# SpaceDisplayOverheadLED_Schematic.net
KiCad netlist of a schematic drawn in Altium Designer
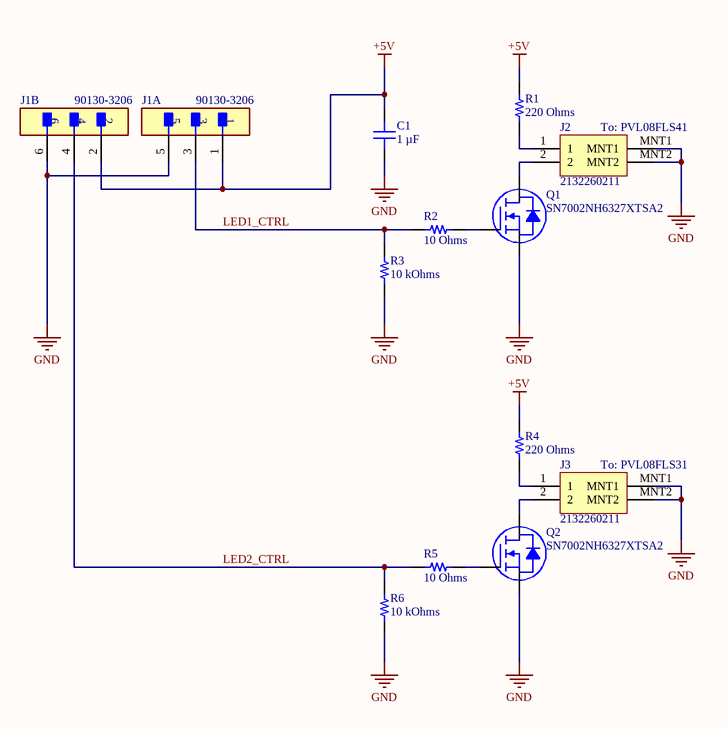
[diagram p0: SpaceDisplayOverheadLED_Schematic.SchDoc]

(export (version "E")
  (design (tool "Eeschema 10.0.6"))
  (components
    (comp (ref "C1")
      (value "1 µF")
      (footprint "CAP 0603_1608")
      (description "CAP CER 1UF 25V X5R 0603")
      (fields
        (field (name "PART NUMBER") "CL10A105KA8NNNC")
        (field (name "CAPACITANCE") "1 µF")
        (field (name "MANUFACTURER") "Samsung Electro-Mechanics")
      )
      (libsource (lib "Celestial Altium Library - altium_library") (part "Capacitor"))
    )
    (comp (ref "J1")
      (value "90130-3206")
      (footprint "FP-90130-3206-MFG")
      (description "90130-3206 Conn Shrouded Header (4 Sides) HDR 6 POS 2.54mm Solder RA Thru-Hole C-Grid III™ Frame")
      (libsource (lib "Altium Content Vault") (part "2654a11fb13586ecb194516b1c997bc"))
    )
    (comp (ref "J2")
      (value "2132260211")
      (footprint "2132260211")
      (libsource (lib "PersonalLibrary") (part "2132260211"))
    )
    (comp (ref "J3")
      (value "2132260211")
      (footprint "2132260211")
      (libsource (lib "PersonalLibrary") (part "2132260211"))
    )
    (comp (ref "Q1")
      (value "SN7002NH6327XTSA2")
      (footprint "INFINEON SOT-23-3")
      (description "MOSFET N-CH 60V 200MA SOT23-3")
      (fields (field (name "MANUFACTURER") "Infineon Technologies"))
      (libsource (lib "Celestial Altium Library - altium_library") (part "INFINEON MOSFET N-CH SOT-23-3 GSD"))
    )
    (comp (ref "Q2")
      (value "SN7002NH6327XTSA2")
      (footprint "INFINEON SOT-23-3")
      (description "MOSFET N-CH 60V 200MA SOT23-3")
      (fields (field (name "MANUFACTURER") "Infineon Technologies"))
      (libsource (lib "Celestial Altium Library - altium_library") (part "INFINEON MOSFET N-CH SOT-23-3 GSD"))
    )
    (comp (ref "R1")
      (value "220 Ohms")
      (footprint "RES 0603_1608")
      (description "RES 220 OHM 1% 1/10W 0603")
      (fields
        (field (name "PART NUMBER") "RMCF0603FT220R")
        (field (name "MANUFACTURER") "Stackpole Electronics Inc")
      )
      (libsource (lib "Celestial Altium Library - altium_library") (part "Resistor"))
    )
    (comp (ref "R2")
      (value "10 Ohms")
      (footprint "RES 0603_1608")
      (description "RES 10 OHM 1% 1/10W 0603")
      (fields
        (field (name "PART NUMBER") "RMCF0603FT10R0")
        (field (name "MANUFACTURER") "Stackpole Electronics Inc")
      )
      (libsource (lib "Celestial Altium Library - altium_library") (part "Resistor"))
    )
    (comp (ref "R3")
      (value "10 kOhms")
      (footprint "RES 0603_1608")
      (description "RES 10K OHM 1% 1/10W 0603")
      (fields
        (field (name "PART NUMBER") "RMCF0603FT10K0")
        (field (name "MANUFACTURER") "Stackpole Electronics Inc")
      )
      (libsource (lib "Celestial Altium Library - altium_library") (part "Resistor"))
    )
    (comp (ref "R4")
      (value "220 Ohms")
      (footprint "RES 0603_1608")
      (description "RES 220 OHM 1% 1/10W 0603")
      (fields
        (field (name "PART NUMBER") "RMCF0603FT220R")
        (field (name "MANUFACTURER") "Stackpole Electronics Inc")
      )
      (libsource (lib "Celestial Altium Library - altium_library") (part "Resistor"))
    )
    (comp (ref "R5")
      (value "10 Ohms")
      (footprint "RES 0603_1608")
      (description "RES 10 OHM 1% 1/10W 0603")
      (fields
        (field (name "PART NUMBER") "RMCF0603FT10R0")
        (field (name "MANUFACTURER") "Stackpole Electronics Inc")
      )
      (libsource (lib "Celestial Altium Library - altium_library") (part "Resistor"))
    )
    (comp (ref "R6")
      (value "10 kOhms")
      (footprint "RES 0603_1608")
      (description "RES 10K OHM 1% 1/10W 0603")
      (fields
        (field (name "PART NUMBER") "RMCF0603FT10K0")
        (field (name "MANUFACTURER") "Stackpole Electronics Inc")
      )
      (libsource (lib "Celestial Altium Library - altium_library") (part "Resistor"))
    )
  )
  (nets
    (net (code "1") (name "+5V") (class "Default")
      (node (ref "C1") (pin "2") (pinfunction "2_2") (pintype "passive"))
      (node (ref "J1") (pin "1") (pinfunction "1_1") (pintype "passive"))
      (node (ref "J1") (pin "2") (pinfunction "2_2") (pintype "passive"))
      (node (ref "R1") (pin "2") (pinfunction "2_2") (pintype "passive"))
      (node (ref "R4") (pin "2") (pinfunction "2_2") (pintype "passive"))
    )
    (net (code "2") (name "/LED1_CTRL") (class "Default")
      (node (ref "J1") (pin "3") (pinfunction "3_3") (pintype "passive"))
      (node (ref "R2") (pin "1") (pinfunction "1_1") (pintype "passive"))
      (node (ref "R3") (pin "2") (pinfunction "2_2") (pintype "passive"))
    )
    (net (code "3") (name "/LED2_CTRL") (class "Default")
      (node (ref "J1") (pin "4") (pinfunction "4_4") (pintype "passive"))
      (node (ref "R5") (pin "1") (pinfunction "1_1") (pintype "passive"))
      (node (ref "R6") (pin "2") (pinfunction "2_2") (pintype "passive"))
    )
    (net (code "4") (name "GND") (class "Default")
      (node (ref "C1") (pin "1") (pinfunction "1_1") (pintype "passive"))
      (node (ref "J1") (pin "5") (pinfunction "5_5") (pintype "passive"))
      (node (ref "J1") (pin "6") (pinfunction "6_6") (pintype "passive"))
      (node (ref "J2") (pin "MNT1") (pinfunction "MNT1_MNT1") (pintype "passive"))
      (node (ref "J2") (pin "MNT2") (pinfunction "MNT2_MNT2") (pintype "passive"))
      (node (ref "J3") (pin "MNT1") (pinfunction "MNT1_MNT1") (pintype "passive"))
      (node (ref "J3") (pin "MNT2") (pinfunction "MNT2_MNT2") (pintype "passive"))
      (node (ref "Q1") (pin "2") (pinfunction "S_2") (pintype "passive"))
      (node (ref "Q2") (pin "2") (pinfunction "S_2") (pintype "passive"))
      (node (ref "R3") (pin "1") (pinfunction "1_1") (pintype "passive"))
      (node (ref "R6") (pin "1") (pinfunction "1_1") (pintype "passive"))
    )
    (net (code "5") (name "Net-(J2-Pad1)") (class "Default")
      (node (ref "J2") (pin "1") (pinfunction "1_1") (pintype "passive"))
      (node (ref "R1") (pin "1") (pinfunction "1_1") (pintype "passive"))
    )
    (net (code "6") (name "Net-(J3-Pad1)") (class "Default")
      (node (ref "J3") (pin "1") (pinfunction "1_1") (pintype "passive"))
      (node (ref "R4") (pin "1") (pinfunction "1_1") (pintype "passive"))
    )
    (net (code "7") (name "Net-(Q1-D)") (class "Default")
      (node (ref "J2") (pin "2") (pinfunction "2_2") (pintype "passive"))
      (node (ref "Q1") (pin "3") (pinfunction "D_3") (pintype "passive"))
    )
    (net (code "8") (name "Net-(Q1-G)") (class "Default")
      (node (ref "Q1") (pin "1") (pinfunction "G_1") (pintype "passive"))
      (node (ref "R2") (pin "2") (pinfunction "2_2") (pintype "passive"))
    )
    (net (code "9") (name "Net-(Q2-D)") (class "Default")
      (node (ref "J3") (pin "2") (pinfunction "2_2") (pintype "passive"))
      (node (ref "Q2") (pin "3") (pinfunction "D_3") (pintype "passive"))
    )
    (net (code "10") (name "Net-(Q2-G)") (class "Default")
      (node (ref "Q2") (pin "1") (pinfunction "G_1") (pintype "passive"))
      (node (ref "R5") (pin "2") (pinfunction "2_2") (pintype "passive"))
    )
  )
)
